# Sheet_Project_Batteries_V2.net
KiCad netlist of a schematic drawn in Altium Designer
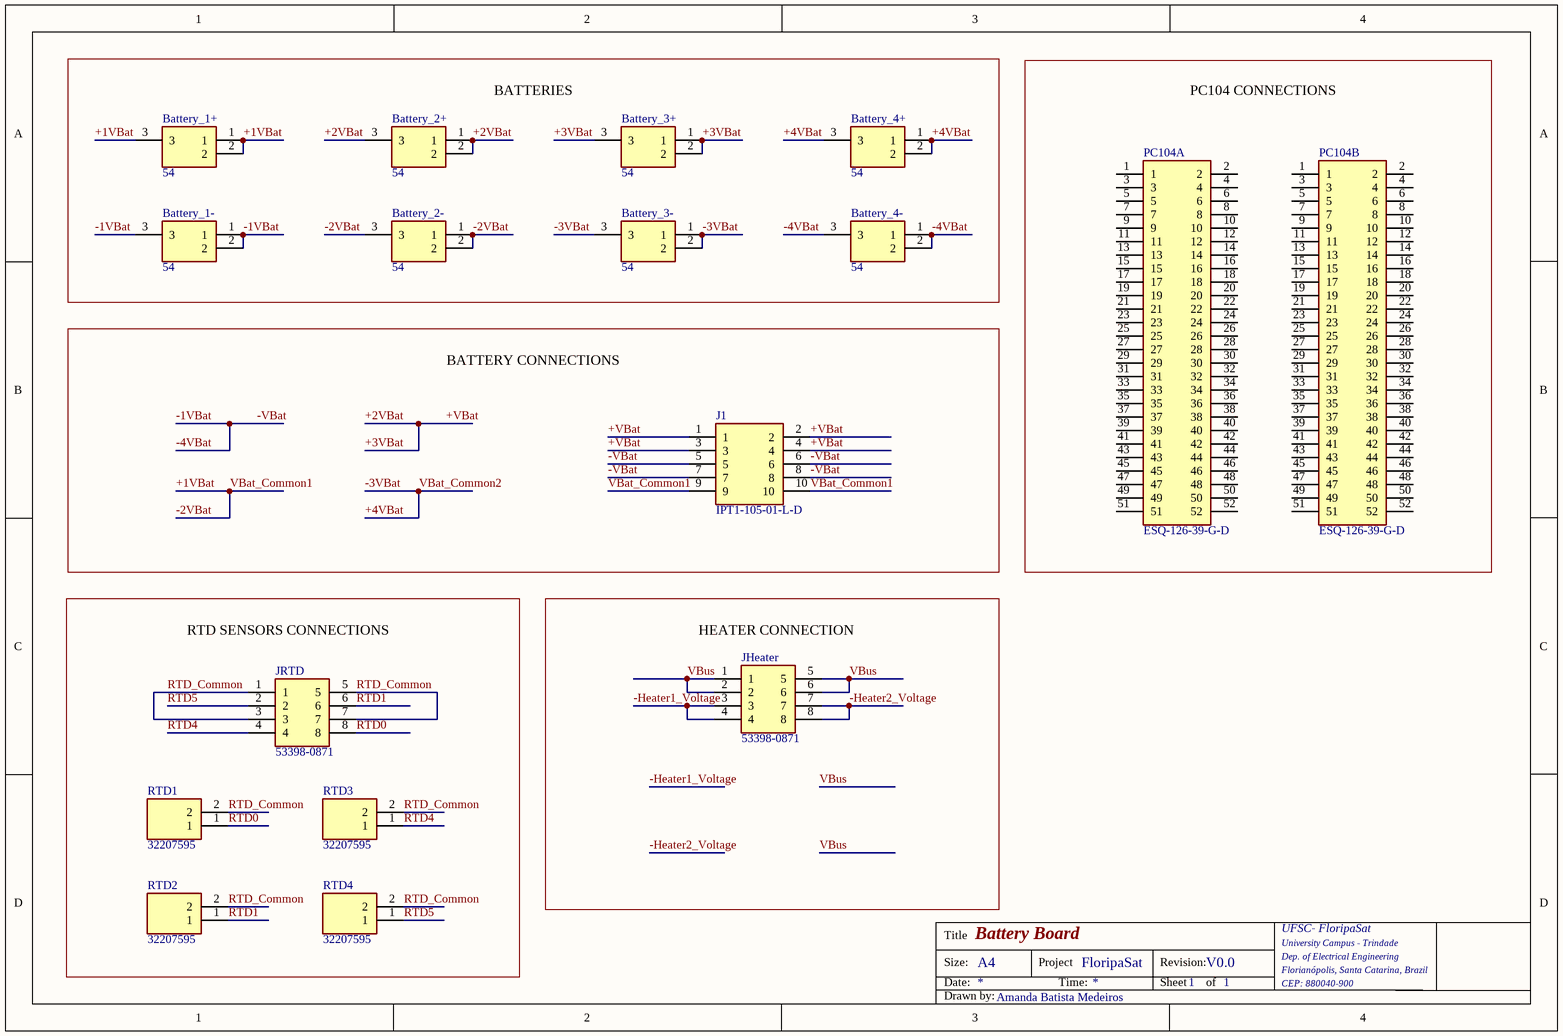
[diagram p0: Sheet_Project_Batteries_V2.SchDoc]

(export (version "E")
  (design (tool "Eeschema 10.0.6"))
  (components
    (comp (ref "Battery_1+")
      (value "54")
      (footprint "SamacSys:54")
      (description "Battery")
      (fields (field (name "MOUSER PART NUMBER") "534-54"))
      (libsource (lib "*") (part "54"))
    )
    (comp (ref "Battery_1-")
      (value "54")
      (footprint "SamacSys:54")
      (description "Battery")
      (fields (field (name "MOUSER PART NUMBER") "534-54"))
      (libsource (lib "*") (part "54"))
    )
    (comp (ref "Battery_2+")
      (value "54")
      (footprint "SamacSys:54")
      (description "Battery")
      (fields (field (name "MOUSER PART NUMBER") "534-54"))
      (libsource (lib "*") (part "54"))
    )
    (comp (ref "Battery_2-")
      (value "54")
      (footprint "SamacSys:54")
      (description "Battery")
      (fields (field (name "MOUSER PART NUMBER") "534-54"))
      (libsource (lib "*") (part "54"))
    )
    (comp (ref "Battery_3+")
      (value "54")
      (footprint "SamacSys:54")
      (description "Battery")
      (fields (field (name "MOUSER PART NUMBER") "534-54"))
      (libsource (lib "*") (part "54"))
    )
    (comp (ref "Battery_3-")
      (value "54")
      (footprint "SamacSys:54")
      (description "Battery")
      (fields (field (name "MOUSER PART NUMBER") "534-54"))
      (libsource (lib "*") (part "54"))
    )
    (comp (ref "Battery_4+")
      (value "54")
      (footprint "SamacSys:54")
      (description "Battery")
      (fields (field (name "MOUSER PART NUMBER") "534-54"))
      (libsource (lib "*") (part "54"))
    )
    (comp (ref "Battery_4-")
      (value "54")
      (footprint "SamacSys:54")
      (description "Battery")
      (fields (field (name "MOUSER PART NUMBER") "534-54"))
      (libsource (lib "*") (part "54"))
    )
    (comp (ref "J1")
      (value "IPT1-105-01-L-D")
      (footprint "SamacSys:RHDR10W64P254_2X5_1321X508X635P")
      (description "Connector")
      (libsource (lib "*") (part "IPT1-105-01-L-D"))
    )
    (comp (ref "JHeater")
      (value "53398-0871")
      (footprint "SamacSys:53398-0871")
      (description "Connector")
      (fields (field (name "MOUSER2 PART NUMBER") "538-53398-0871"))
      (libsource (lib "*") (part "53398-0871"))
    )
    (comp (ref "JRTD")
      (value "53398-0871")
      (footprint "SamacSys:53398-0871")
      (description "Connector")
      (fields (field (name "MOUSER2 PART NUMBER") "538-53398-0871"))
      (libsource (lib "*") (part "53398-0871"))
    )
    (comp (ref "PC104A")
      (value "ESQ-126-39-G-D")
      (footprint "SamacSys:SHDR52W64P254_2X26_6550X495X1384P")
      (description "Connector")
      (fields (field (name "MOUSER PART NUMBER") "200-ESQ12639GD") (field (name "RS PART NUMBER") "1595654"))
      (libsource (lib "*") (part "ESQ-126-39-G-D"))
    )
    (comp (ref "PC104B")
      (value "ESQ-126-39-G-D")
      (footprint "SamacSys:SHDR52W64P254_2X26_6550X495X1384P")
      (description "Connector")
      (fields (field (name "MOUSER PART NUMBER") "200-ESQ12639GD") (field (name "RS PART NUMBER") "1595654"))
      (libsource (lib "*") (part "ESQ-126-39-G-D"))
    )
    (comp (ref "RTD1")
      (value "32207595")
      (footprint "SamacSys:THRMC3216X70N")
      (description "Integrated Circuit")
      (libsource (lib "*") (part "32207595"))
    )
    (comp (ref "RTD2")
      (value "32207595")
      (footprint "SamacSys:THRMC3216X70N")
      (description "Integrated Circuit")
      (libsource (lib "*") (part "32207595"))
    )
    (comp (ref "RTD3")
      (value "32207595")
      (footprint "SamacSys:THRMC3216X70N")
      (description "Integrated Circuit")
      (libsource (lib "*") (part "32207595"))
    )
    (comp (ref "RTD4")
      (value "32207595")
      (footprint "SamacSys:THRMC3216X70N")
      (description "Integrated Circuit")
      (libsource (lib "*") (part "32207595"))
    )
  )
  (nets
    (net (code "1") (name "/+1VBat") (class "Default")
      (node (ref "Battery_1+") (pin "1") (pinfunction "1_1") (pintype "passive"))
      (node (ref "Battery_1+") (pin "2") (pinfunction "2_2") (pintype "passive"))
      (node (ref "Battery_1+") (pin "3") (pinfunction "3_3") (pintype "passive"))
      (node (ref "Battery_2-") (pin "1") (pinfunction "1_1") (pintype "passive"))
      (node (ref "Battery_2-") (pin "2") (pinfunction "2_2") (pintype "passive"))
      (node (ref "Battery_2-") (pin "3") (pinfunction "3_3") (pintype "passive"))
      (node (ref "J1") (pin "10") (pinfunction "10_10") (pintype "passive"))
      (node (ref "J1") (pin "9") (pinfunction "9_9") (pintype "passive"))
    )
    (net (code "2") (name "/+2VBat") (class "Default")
      (node (ref "Battery_2+") (pin "1") (pinfunction "1_1") (pintype "passive"))
      (node (ref "Battery_2+") (pin "2") (pinfunction "2_2") (pintype "passive"))
      (node (ref "Battery_2+") (pin "3") (pinfunction "3_3") (pintype "passive"))
      (node (ref "Battery_3+") (pin "1") (pinfunction "1_1") (pintype "passive"))
      (node (ref "Battery_3+") (pin "2") (pinfunction "2_2") (pintype "passive"))
      (node (ref "Battery_3+") (pin "3") (pinfunction "3_3") (pintype "passive"))
      (node (ref "J1") (pin "1") (pinfunction "1_1") (pintype "passive"))
      (node (ref "J1") (pin "2") (pinfunction "2_2") (pintype "passive"))
      (node (ref "J1") (pin "3") (pinfunction "3_3") (pintype "passive"))
      (node (ref "J1") (pin "4") (pinfunction "4_4") (pintype "passive"))
    )
    (net (code "3") (name "/+4VBat") (class "Default")
      (node (ref "Battery_3-") (pin "1") (pinfunction "1_1") (pintype "passive"))
      (node (ref "Battery_3-") (pin "2") (pinfunction "2_2") (pintype "passive"))
      (node (ref "Battery_3-") (pin "3") (pinfunction "3_3") (pintype "passive"))
      (node (ref "Battery_4+") (pin "1") (pinfunction "1_1") (pintype "passive"))
      (node (ref "Battery_4+") (pin "2") (pinfunction "2_2") (pintype "passive"))
      (node (ref "Battery_4+") (pin "3") (pinfunction "3_3") (pintype "passive"))
    )
    (net (code "4") (name "/-1VBat") (class "Default")
      (node (ref "Battery_1-") (pin "1") (pinfunction "1_1") (pintype "passive"))
      (node (ref "Battery_1-") (pin "2") (pinfunction "2_2") (pintype "passive"))
      (node (ref "Battery_1-") (pin "3") (pinfunction "3_3") (pintype "passive"))
      (node (ref "Battery_4-") (pin "1") (pinfunction "1_1") (pintype "passive"))
      (node (ref "Battery_4-") (pin "2") (pinfunction "2_2") (pintype "passive"))
      (node (ref "Battery_4-") (pin "3") (pinfunction "3_3") (pintype "passive"))
      (node (ref "J1") (pin "5") (pinfunction "5_5") (pintype "passive"))
      (node (ref "J1") (pin "6") (pinfunction "6_6") (pintype "passive"))
      (node (ref "J1") (pin "7") (pinfunction "7_7") (pintype "passive"))
      (node (ref "J1") (pin "8") (pinfunction "8_8") (pintype "passive"))
    )
    (net (code "5") (name "/-Heater1_Voltage") (class "Default")
      (node (ref "JHeater") (pin "3") (pinfunction "3_3") (pintype "passive"))
      (node (ref "JHeater") (pin "4") (pinfunction "4_4") (pintype "passive"))
    )
    (net (code "6") (name "/-Heater2_Voltage") (class "Default")
      (node (ref "JHeater") (pin "7") (pinfunction "7_7") (pintype "passive"))
      (node (ref "JHeater") (pin "8") (pinfunction "8_8") (pintype "passive"))
    )
    (net (code "7") (name "/RTD0") (class "Default")
      (node (ref "JRTD") (pin "8") (pinfunction "8_8") (pintype "passive"))
      (node (ref "RTD1") (pin "1") (pinfunction "1_1") (pintype "passive"))
    )
    (net (code "8") (name "/RTD1") (class "Default")
      (node (ref "JRTD") (pin "6") (pinfunction "6_6") (pintype "passive"))
      (node (ref "RTD2") (pin "1") (pinfunction "1_1") (pintype "passive"))
    )
    (net (code "9") (name "/RTD4") (class "Default")
      (node (ref "JRTD") (pin "4") (pinfunction "4_4") (pintype "passive"))
      (node (ref "RTD3") (pin "1") (pinfunction "1_1") (pintype "passive"))
    )
    (net (code "10") (name "/RTD5") (class "Default")
      (node (ref "JRTD") (pin "2") (pinfunction "2_2") (pintype "passive"))
      (node (ref "RTD4") (pin "1") (pinfunction "1_1") (pintype "passive"))
    )
    (net (code "11") (name "/RTD_Common") (class "Default")
      (node (ref "JRTD") (pin "1") (pinfunction "1_1") (pintype "passive"))
      (node (ref "JRTD") (pin "3") (pinfunction "3_3") (pintype "passive"))
      (node (ref "JRTD") (pin "5") (pinfunction "5_5") (pintype "passive"))
      (node (ref "JRTD") (pin "7") (pinfunction "7_7") (pintype "passive"))
      (node (ref "RTD1") (pin "2") (pinfunction "2_2") (pintype "passive"))
      (node (ref "RTD2") (pin "2") (pinfunction "2_2") (pintype "passive"))
      (node (ref "RTD3") (pin "2") (pinfunction "2_2") (pintype "passive"))
      (node (ref "RTD4") (pin "2") (pinfunction "2_2") (pintype "passive"))
    )
    (net (code "12") (name "/VBus") (class "Default")
      (node (ref "JHeater") (pin "1") (pinfunction "1_1") (pintype "passive"))
      (node (ref "JHeater") (pin "2") (pinfunction "2_2") (pintype "passive"))
      (node (ref "JHeater") (pin "5") (pinfunction "5_5") (pintype "passive"))
      (node (ref "JHeater") (pin "6") (pinfunction "6_6") (pintype "passive"))
    )
    (net (code "13") (name "unconnected-(PC104A-Pad1)") (class "Default")
      (node (ref "PC104A") (pin "1") (pinfunction "1_1") (pintype "passive"))
    )
    (net (code "14") (name "unconnected-(PC104A-Pad2)") (class "Default")
      (node (ref "PC104A") (pin "2") (pinfunction "2_2") (pintype "passive"))
    )
    (net (code "15") (name "unconnected-(PC104A-Pad3)") (class "Default")
      (node (ref "PC104A") (pin "3") (pinfunction "3_3") (pintype "passive"))
    )
    (net (code "16") (name "unconnected-(PC104A-Pad4)") (class "Default")
      (node (ref "PC104A") (pin "4") (pinfunction "4_4") (pintype "passive"))
    )
    (net (code "17") (name "unconnected-(PC104A-Pad5)") (class "Default")
      (node (ref "PC104A") (pin "5") (pinfunction "5_5") (pintype "passive"))
    )
    (net (code "18") (name "unconnected-(PC104A-Pad6)") (class "Default")
      (node (ref "PC104A") (pin "6") (pinfunction "6_6") (pintype "passive"))
    )
    (net (code "19") (name "unconnected-(PC104A-Pad7)") (class "Default")
      (node (ref "PC104A") (pin "7") (pinfunction "7_7") (pintype "passive"))
    )
    (net (code "20") (name "unconnected-(PC104A-Pad8)") (class "Default")
      (node (ref "PC104A") (pin "8") (pinfunction "8_8") (pintype "passive"))
    )
    (net (code "21") (name "unconnected-(PC104A-Pad9)") (class "Default")
      (node (ref "PC104A") (pin "9") (pinfunction "9_9") (pintype "passive"))
    )
    (net (code "22") (name "unconnected-(PC104A-Pad10)") (class "Default")
      (node (ref "PC104A") (pin "10") (pinfunction "10_10") (pintype "passive"))
    )
    (net (code "23") (name "unconnected-(PC104A-Pad11)") (class "Default")
      (node (ref "PC104A") (pin "11") (pinfunction "11_11") (pintype "passive"))
    )
    (net (code "24") (name "unconnected-(PC104A-Pad12)") (class "Default")
      (node (ref "PC104A") (pin "12") (pinfunction "12_12") (pintype "passive"))
    )
    (net (code "25") (name "unconnected-(PC104A-Pad13)") (class "Default")
      (node (ref "PC104A") (pin "13") (pinfunction "13_13") (pintype "passive"))
    )
    (net (code "26") (name "unconnected-(PC104A-Pad14)") (class "Default")
      (node (ref "PC104A") (pin "14") (pinfunction "14_14") (pintype "passive"))
    )
    (net (code "27") (name "unconnected-(PC104A-Pad15)") (class "Default")
      (node (ref "PC104A") (pin "15") (pinfunction "15_15") (pintype "passive"))
    )
    (net (code "28") (name "unconnected-(PC104A-Pad16)") (class "Default")
      (node (ref "PC104A") (pin "16") (pinfunction "16_16") (pintype "passive"))
    )
    (net (code "29") (name "unconnected-(PC104A-Pad17)") (class "Default")
      (node (ref "PC104A") (pin "17") (pinfunction "17_17") (pintype "passive"))
    )
    (net (code "30") (name "unconnected-(PC104A-Pad18)") (class "Default")
      (node (ref "PC104A") (pin "18") (pinfunction "18_18") (pintype "passive"))
    )
    (net (code "31") (name "unconnected-(PC104A-Pad19)") (class "Default")
      (node (ref "PC104A") (pin "19") (pinfunction "19_19") (pintype "passive"))
    )
    (net (code "32") (name "unconnected-(PC104A-Pad20)") (class "Default")
      (node (ref "PC104A") (pin "20") (pinfunction "20_20") (pintype "passive"))
    )
    (net (code "33") (name "unconnected-(PC104A-Pad21)") (class "Default")
      (node (ref "PC104A") (pin "21") (pinfunction "21_21") (pintype "passive"))
    )
    (net (code "34") (name "unconnected-(PC104A-Pad22)") (class "Default")
      (node (ref "PC104A") (pin "22") (pinfunction "22_22") (pintype "passive"))
    )
    (net (code "35") (name "unconnected-(PC104A-Pad23)") (class "Default")
      (node (ref "PC104A") (pin "23") (pinfunction "23_23") (pintype "passive"))
    )
    (net (code "36") (name "unconnected-(PC104A-Pad24)") (class "Default")
      (node (ref "PC104A") (pin "24") (pinfunction "24_24") (pintype "passive"))
    )
    (net (code "37") (name "unconnected-(PC104A-Pad25)") (class "Default")
      (node (ref "PC104A") (pin "25") (pinfunction "25_25") (pintype "passive"))
    )
    (net (code "38") (name "unconnected-(PC104A-Pad26)") (class "Default")
      (node (ref "PC104A") (pin "26") (pinfunction "26_26") (pintype "passive"))
    )
    (net (code "39") (name "unconnected-(PC104A-Pad27)") (class "Default")
      (node (ref "PC104A") (pin "27") (pinfunction "27_27") (pintype "passive"))
    )
    (net (code "40") (name "unconnected-(PC104A-Pad28)") (class "Default")
      (node (ref "PC104A") (pin "28") (pinfunction "28_28") (pintype "passive"))
    )
    (net (code "41") (name "unconnected-(PC104A-Pad29)") (class "Default")
      (node (ref "PC104A") (pin "29") (pinfunction "29_29") (pintype "passive"))
    )
    (net (code "42") (name "unconnected-(PC104A-Pad30)") (class "Default")
      (node (ref "PC104A") (pin "30") (pinfunction "30_30") (pintype "passive"))
    )
    (net (code "43") (name "unconnected-(PC104A-Pad31)") (class "Default")
      (node (ref "PC104A") (pin "31") (pinfunction "31_31") (pintype "passive"))
    )
    (net (code "44") (name "unconnected-(PC104A-Pad32)") (class "Default")
      (node (ref "PC104A") (pin "32") (pinfunction "32_32") (pintype "passive"))
    )
    (net (code "45") (name "unconnected-(PC104A-Pad33)") (class "Default")
      (node (ref "PC104A") (pin "33") (pinfunction "33_33") (pintype "passive"))
    )
    (net (code "46") (name "unconnected-(PC104A-Pad34)") (class "Default")
      (node (ref "PC104A") (pin "34") (pinfunction "34_34") (pintype "passive"))
    )
    (net (code "47") (name "unconnected-(PC104A-Pad35)") (class "Default")
      (node (ref "PC104A") (pin "35") (pinfunction "35_35") (pintype "passive"))
    )
    (net (code "48") (name "unconnected-(PC104A-Pad36)") (class "Default")
      (node (ref "PC104A") (pin "36") (pinfunction "36_36") (pintype "passive"))
    )
    (net (code "49") (name "unconnected-(PC104A-Pad37)") (class "Default")
      (node (ref "PC104A") (pin "37") (pinfunction "37_37") (pintype "passive"))
    )
    (net (code "50") (name "unconnected-(PC104A-Pad38)") (class "Default")
      (node (ref "PC104A") (pin "38") (pinfunction "38_38") (pintype "passive"))
    )
    (net (code "51") (name "unconnected-(PC104A-Pad39)") (class "Default")
      (node (ref "PC104A") (pin "39") (pinfunction "39_39") (pintype "passive"))
    )
    (net (code "52") (name "unconnected-(PC104A-Pad40)") (class "Default")
      (node (ref "PC104A") (pin "40") (pinfunction "40_40") (pintype "passive"))
    )
    (net (code "53") (name "unconnected-(PC104A-Pad41)") (class "Default")
      (node (ref "PC104A") (pin "41") (pinfunction "41_41") (pintype "passive"))
    )
    (net (code "54") (name "unconnected-(PC104A-Pad42)") (class "Default")
      (node (ref "PC104A") (pin "42") (pinfunction "42_42") (pintype "passive"))
    )
    (net (code "55") (name "unconnected-(PC104A-Pad43)") (class "Default")
      (node (ref "PC104A") (pin "43") (pinfunction "43_43") (pintype "passive"))
    )
    (net (code "56") (name "unconnected-(PC104A-Pad44)") (class "Default")
      (node (ref "PC104A") (pin "44") (pinfunction "44_44") (pintype "passive"))
    )
    (net (code "57") (name "unconnected-(PC104A-Pad45)") (class "Default")
      (node (ref "PC104A") (pin "45") (pinfunction "45_45") (pintype "passive"))
    )
    (net (code "58") (name "unconnected-(PC104A-Pad46)") (class "Default")
      (node (ref "PC104A") (pin "46") (pinfunction "46_46") (pintype "passive"))
    )
    (net (code "59") (name "unconnected-(PC104A-Pad47)") (class "Default")
      (node (ref "PC104A") (pin "47") (pinfunction "47_47") (pintype "passive"))
    )
    (net (code "60") (name "unconnected-(PC104A-Pad48)") (class "Default")
      (node (ref "PC104A") (pin "48") (pinfunction "48_48") (pintype "passive"))
    )
    (net (code "61") (name "unconnected-(PC104A-Pad49)") (class "Default")
      (node (ref "PC104A") (pin "49") (pinfunction "49_49") (pintype "passive"))
    )
    (net (code "62") (name "unconnected-(PC104A-Pad50)") (class "Default")
      (node (ref "PC104A") (pin "50") (pinfunction "50_50") (pintype "passive"))
    )
    (net (code "63") (name "unconnected-(PC104A-Pad51)") (class "Default")
      (node (ref "PC104A") (pin "51") (pinfunction "51_51") (pintype "passive"))
    )
    (net (code "64") (name "unconnected-(PC104A-Pad52)") (class "Default")
      (node (ref "PC104A") (pin "52") (pinfunction "52_52") (pintype "passive"))
    )
    (net (code "65") (name "unconnected-(PC104B-Pad1)") (class "Default")
      (node (ref "PC104B") (pin "1") (pinfunction "1_1") (pintype "passive"))
    )
    (net (code "66") (name "unconnected-(PC104B-Pad2)") (class "Default")
      (node (ref "PC104B") (pin "2") (pinfunction "2_2") (pintype "passive"))
    )
    (net (code "67") (name "unconnected-(PC104B-Pad3)") (class "Default")
      (node (ref "PC104B") (pin "3") (pinfunction "3_3") (pintype "passive"))
    )
    (net (code "68") (name "unconnected-(PC104B-Pad4)") (class "Default")
      (node (ref "PC104B") (pin "4") (pinfunction "4_4") (pintype "passive"))
    )
    (net (code "69") (name "unconnected-(PC104B-Pad5)") (class "Default")
      (node (ref "PC104B") (pin "5") (pinfunction "5_5") (pintype "passive"))
    )
    (net (code "70") (name "unconnected-(PC104B-Pad6)") (class "Default")
      (node (ref "PC104B") (pin "6") (pinfunction "6_6") (pintype "passive"))
    )
    (net (code "71") (name "unconnected-(PC104B-Pad7)") (class "Default")
      (node (ref "PC104B") (pin "7") (pinfunction "7_7") (pintype "passive"))
    )
    (net (code "72") (name "unconnected-(PC104B-Pad8)") (class "Default")
      (node (ref "PC104B") (pin "8") (pinfunction "8_8") (pintype "passive"))
    )
    (net (code "73") (name "unconnected-(PC104B-Pad9)") (class "Default")
      (node (ref "PC104B") (pin "9") (pinfunction "9_9") (pintype "passive"))
    )
    (net (code "74") (name "unconnected-(PC104B-Pad10)") (class "Default")
      (node (ref "PC104B") (pin "10") (pinfunction "10_10") (pintype "passive"))
    )
    (net (code "75") (name "unconnected-(PC104B-Pad11)") (class "Default")
      (node (ref "PC104B") (pin "11") (pinfunction "11_11") (pintype "passive"))
    )
    (net (code "76") (name "unconnected-(PC104B-Pad12)") (class "Default")
      (node (ref "PC104B") (pin "12") (pinfunction "12_12") (pintype "passive"))
    )
    (net (code "77") (name "unconnected-(PC104B-Pad13)") (class "Default")
      (node (ref "PC104B") (pin "13") (pinfunction "13_13") (pintype "passive"))
    )
    (net (code "78") (name "unconnected-(PC104B-Pad14)") (class "Default")
      (node (ref "PC104B") (pin "14") (pinfunction "14_14") (pintype "passive"))
    )
    (net (code "79") (name "unconnected-(PC104B-Pad15)") (class "Default")
      (node (ref "PC104B") (pin "15") (pinfunction "15_15") (pintype "passive"))
    )
    (net (code "80") (name "unconnected-(PC104B-Pad16)") (class "Default")
      (node (ref "PC104B") (pin "16") (pinfunction "16_16") (pintype "passive"))
    )
    (net (code "81") (name "unconnected-(PC104B-Pad17)") (class "Default")
      (node (ref "PC104B") (pin "17") (pinfunction "17_17") (pintype "passive"))
    )
    (net (code "82") (name "unconnected-(PC104B-Pad18)") (class "Default")
      (node (ref "PC104B") (pin "18") (pinfunction "18_18") (pintype "passive"))
    )
    (net (code "83") (name "unconnected-(PC104B-Pad19)") (class "Default")
      (node (ref "PC104B") (pin "19") (pinfunction "19_19") (pintype "passive"))
    )
    (net (code "84") (name "unconnected-(PC104B-Pad20)") (class "Default")
      (node (ref "PC104B") (pin "20") (pinfunction "20_20") (pintype "passive"))
    )
    (net (code "85") (name "unconnected-(PC104B-Pad21)") (class "Default")
      (node (ref "PC104B") (pin "21") (pinfunction "21_21") (pintype "passive"))
    )
    (net (code "86") (name "unconnected-(PC104B-Pad22)") (class "Default")
      (node (ref "PC104B") (pin "22") (pinfunction "22_22") (pintype "passive"))
    )
    (net (code "87") (name "unconnected-(PC104B-Pad23)") (class "Default")
      (node (ref "PC104B") (pin "23") (pinfunction "23_23") (pintype "passive"))
    )
    (net (code "88") (name "unconnected-(PC104B-Pad24)") (class "Default")
      (node (ref "PC104B") (pin "24") (pinfunction "24_24") (pintype "passive"))
    )
    (net (code "89") (name "unconnected-(PC104B-Pad25)") (class "Default")
      (node (ref "PC104B") (pin "25") (pinfunction "25_25") (pintype "passive"))
    )
    (net (code "90") (name "unconnected-(PC104B-Pad26)") (class "Default")
      (node (ref "PC104B") (pin "26") (pinfunction "26_26") (pintype "passive"))
    )
    (net (code "91") (name "unconnected-(PC104B-Pad27)") (class "Default")
      (node (ref "PC104B") (pin "27") (pinfunction "27_27") (pintype "passive"))
    )
    (net (code "92") (name "unconnected-(PC104B-Pad28)") (class "Default")
      (node (ref "PC104B") (pin "28") (pinfunction "28_28") (pintype "passive"))
    )
    (net (code "93") (name "unconnected-(PC104B-Pad29)") (class "Default")
      (node (ref "PC104B") (pin "29") (pinfunction "29_29") (pintype "passive"))
    )
    (net (code "94") (name "unconnected-(PC104B-Pad30)") (class "Default")
      (node (ref "PC104B") (pin "30") (pinfunction "30_30") (pintype "passive"))
    )
    (net (code "95") (name "unconnected-(PC104B-Pad31)") (class "Default")
      (node (ref "PC104B") (pin "31") (pinfunction "31_31") (pintype "passive"))
    )
    (net (code "96") (name "unconnected-(PC104B-Pad32)") (class "Default")
      (node (ref "PC104B") (pin "32") (pinfunction "32_32") (pintype "passive"))
    )
    (net (code "97") (name "unconnected-(PC104B-Pad33)") (class "Default")
      (node (ref "PC104B") (pin "33") (pinfunction "33_33") (pintype "passive"))
    )
    (net (code "98") (name "unconnected-(PC104B-Pad34)") (class "Default")
      (node (ref "PC104B") (pin "34") (pinfunction "34_34") (pintype "passive"))
    )
    (net (code "99") (name "unconnected-(PC104B-Pad35)") (class "Default")
      (node (ref "PC104B") (pin "35") (pinfunction "35_35") (pintype "passive"))
    )
    (net (code "100") (name "unconnected-(PC104B-Pad36)") (class "Default")
      (node (ref "PC104B") (pin "36") (pinfunction "36_36") (pintype "passive"))
    )
    (net (code "101") (name "unconnected-(PC104B-Pad37)") (class "Default")
      (node (ref "PC104B") (pin "37") (pinfunction "37_37") (pintype "passive"))
    )
    (net (code "102") (name "unconnected-(PC104B-Pad38)") (class "Default")
      (node (ref "PC104B") (pin "38") (pinfunction "38_38") (pintype "passive"))
    )
    (net (code "103") (name "unconnected-(PC104B-Pad39)") (class "Default")
      (node (ref "PC104B") (pin "39") (pinfunction "39_39") (pintype "passive"))
    )
    (net (code "104") (name "unconnected-(PC104B-Pad40)") (class "Default")
      (node (ref "PC104B") (pin "40") (pinfunction "40_40") (pintype "passive"))
    )
    (net (code "105") (name "unconnected-(PC104B-Pad41)") (class "Default")
      (node (ref "PC104B") (pin "41") (pinfunction "41_41") (pintype "passive"))
    )
    (net (code "106") (name "unconnected-(PC104B-Pad42)") (class "Default")
      (node (ref "PC104B") (pin "42") (pinfunction "42_42") (pintype "passive"))
    )
    (net (code "107") (name "unconnected-(PC104B-Pad43)") (class "Default")
      (node (ref "PC104B") (pin "43") (pinfunction "43_43") (pintype "passive"))
    )
    (net (code "108") (name "unconnected-(PC104B-Pad44)") (class "Default")
      (node (ref "PC104B") (pin "44") (pinfunction "44_44") (pintype "passive"))
    )
    (net (code "109") (name "unconnected-(PC104B-Pad45)") (class "Default")
      (node (ref "PC104B") (pin "45") (pinfunction "45_45") (pintype "passive"))
    )
    (net (code "110") (name "unconnected-(PC104B-Pad46)") (class "Default")
      (node (ref "PC104B") (pin "46") (pinfunction "46_46") (pintype "passive"))
    )
    (net (code "111") (name "unconnected-(PC104B-Pad47)") (class "Default")
      (node (ref "PC104B") (pin "47") (pinfunction "47_47") (pintype "passive"))
    )
    (net (code "112") (name "unconnected-(PC104B-Pad48)") (class "Default")
      (node (ref "PC104B") (pin "48") (pinfunction "48_48") (pintype "passive"))
    )
    (net (code "113") (name "unconnected-(PC104B-Pad49)") (class "Default")
      (node (ref "PC104B") (pin "49") (pinfunction "49_49") (pintype "passive"))
    )
    (net (code "114") (name "unconnected-(PC104B-Pad50)") (class "Default")
      (node (ref "PC104B") (pin "50") (pinfunction "50_50") (pintype "passive"))
    )
    (net (code "115") (name "unconnected-(PC104B-Pad51)") (class "Default")
      (node (ref "PC104B") (pin "51") (pinfunction "51_51") (pintype "passive"))
    )
    (net (code "116") (name "unconnected-(PC104B-Pad52)") (class "Default")
      (node (ref "PC104B") (pin "52") (pinfunction "52_52") (pintype "passive"))
    )
  )
)
